# finalFilter.net
KiCad netlist of a schematic drawn in Altium Designer
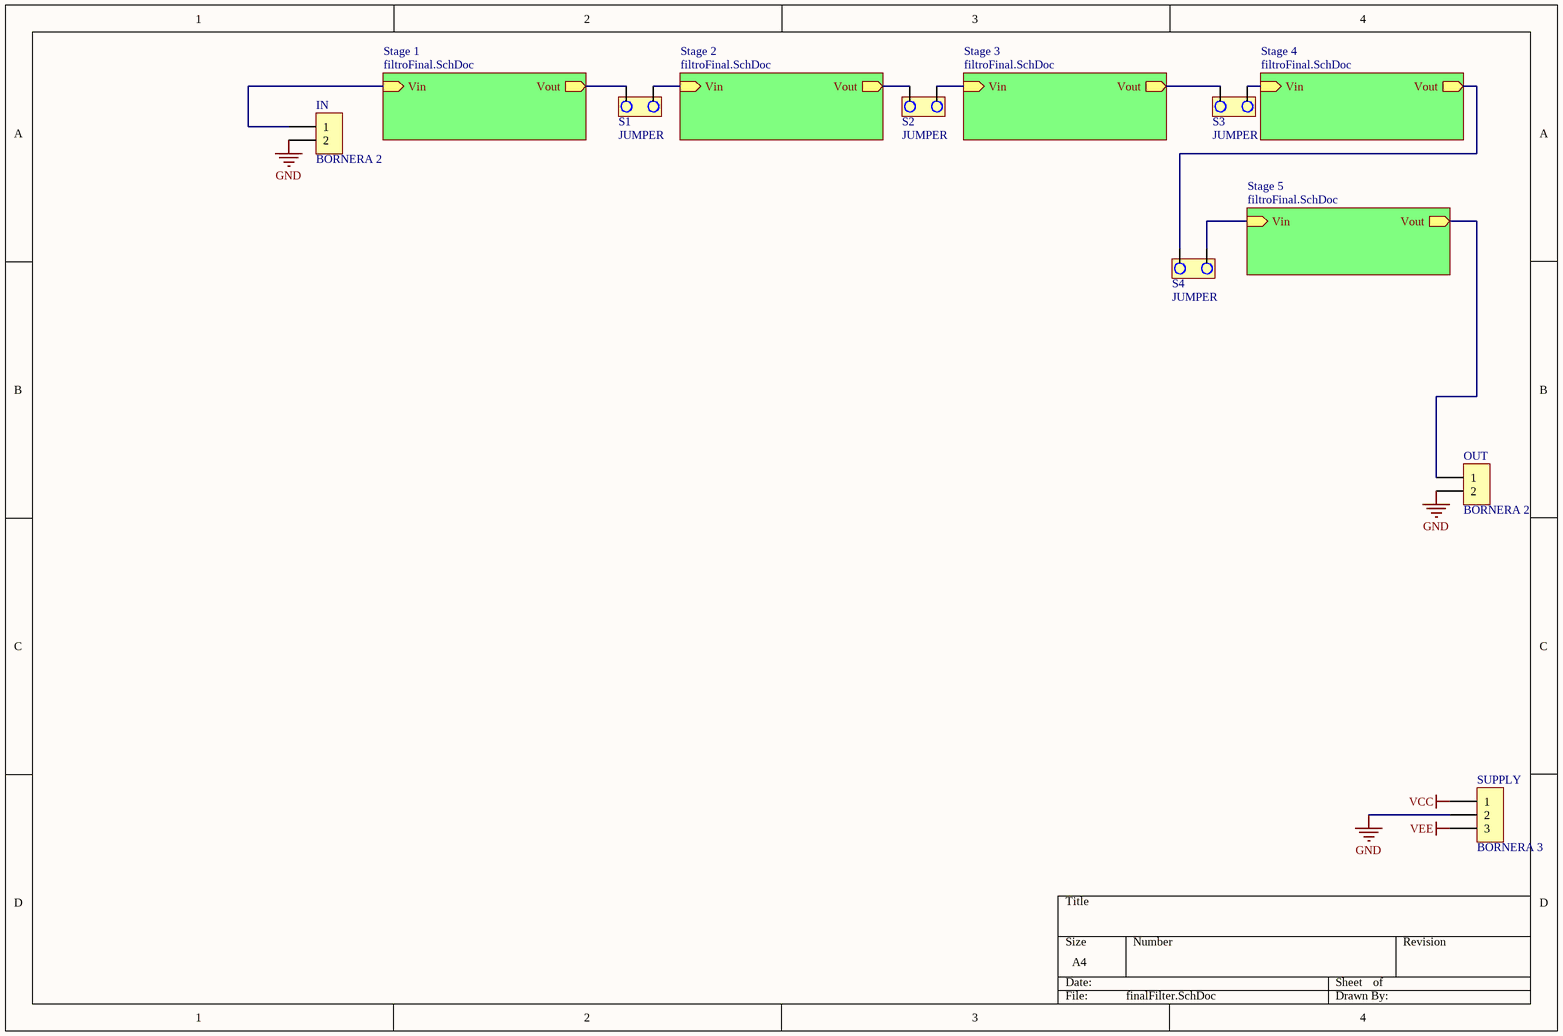
[diagram p0: finalFilter.SchDoc]

(export (version "E")
  (design (tool "Eeschema 10.0.6"))
  (components
    (comp (ref "IN")
      (value "BORNERA 2")
      (footprint "BORNERA2")
      (libsource (lib "LIBEBAL") (part "BORNERA 2"))
    )
    (comp (ref "OUT")
      (value "BORNERA 2")
      (footprint "BORNERA2")
      (libsource (lib "LIBEBAL") (part "BORNERA 2"))
    )
    (comp (ref "S1") (value "JUMPER") (footprint "JUMPER2") (libsource (lib "LIBEBAL") (part "JUMPER")))
    (comp (ref "S2") (value "JUMPER") (footprint "JUMPER2") (libsource (lib "LIBEBAL") (part "JUMPER")))
    (comp (ref "S3") (value "JUMPER") (footprint "JUMPER2") (libsource (lib "LIBEBAL") (part "JUMPER")))
    (comp (ref "S4") (value "JUMPER") (footprint "JUMPER2") (libsource (lib "LIBEBAL") (part "JUMPER")))
    (comp (ref "SUPPLY")
      (value "BORNERA 3")
      (footprint "BORNERA3")
      (libsource (lib "LIBEBAL") (part "BORNERA 3"))
    )
  )
  (nets
    (net (code "1") (name "/Vin") (class "Default")
      (node (ref "S1") (pin "2") (pinfunction "2_2") (pintype "passive"))
    )
    (net (code "2") (name "/Vin_1") (class "Default")
      (node (ref "IN") (pin "1") (pinfunction "1_1") (pintype "passive"))
    )
    (net (code "3") (name "/Vin_2") (class "Default")
      (node (ref "S3") (pin "2") (pinfunction "2_2") (pintype "passive"))
    )
    (net (code "4") (name "/Vin_3") (class "Default")
      (node (ref "S2") (pin "2") (pinfunction "2_2") (pintype "passive"))
    )
    (net (code "5") (name "/Vin_4") (class "Default")
      (node (ref "S4") (pin "2") (pinfunction "2_2") (pintype "passive"))
    )
    (net (code "6") (name "/Vout") (class "Default")
      (node (ref "S1") (pin "1") (pinfunction "1_1") (pintype "passive"))
    )
    (net (code "7") (name "/Vout_1") (class "Default")
      (node (ref "S3") (pin "1") (pinfunction "1_1") (pintype "passive"))
    )
    (net (code "8") (name "/Vout_2") (class "Default")
      (node (ref "S4") (pin "1") (pinfunction "1_1") (pintype "passive"))
    )
    (net (code "9") (name "/Vout_3") (class "Default")
      (node (ref "S2") (pin "1") (pinfunction "1_1") (pintype "passive"))
    )
    (net (code "10") (name "/Vout_4") (class "Default")
      (node (ref "OUT") (pin "1") (pinfunction "1_1") (pintype "passive"))
    )
    (net (code "11") (name "GND") (class "Default")
      (node (ref "IN") (pin "2") (pinfunction "2_2") (pintype "passive"))
      (node (ref "OUT") (pin "2") (pinfunction "2_2") (pintype "passive"))
      (node (ref "SUPPLY") (pin "2") (pinfunction "2_2") (pintype "passive"))
    )
    (net (code "12") (name "VCC") (class "Default")
      (node (ref "SUPPLY") (pin "1") (pinfunction "1_1") (pintype "passive"))
    )
    (net (code "13") (name "VEE") (class "Default")
      (node (ref "SUPPLY") (pin "3") (pinfunction "3_3") (pintype "passive"))
    )
  )
)
